# IRSensor.net
KiCad netlist of a schematic drawn in Altium Designer
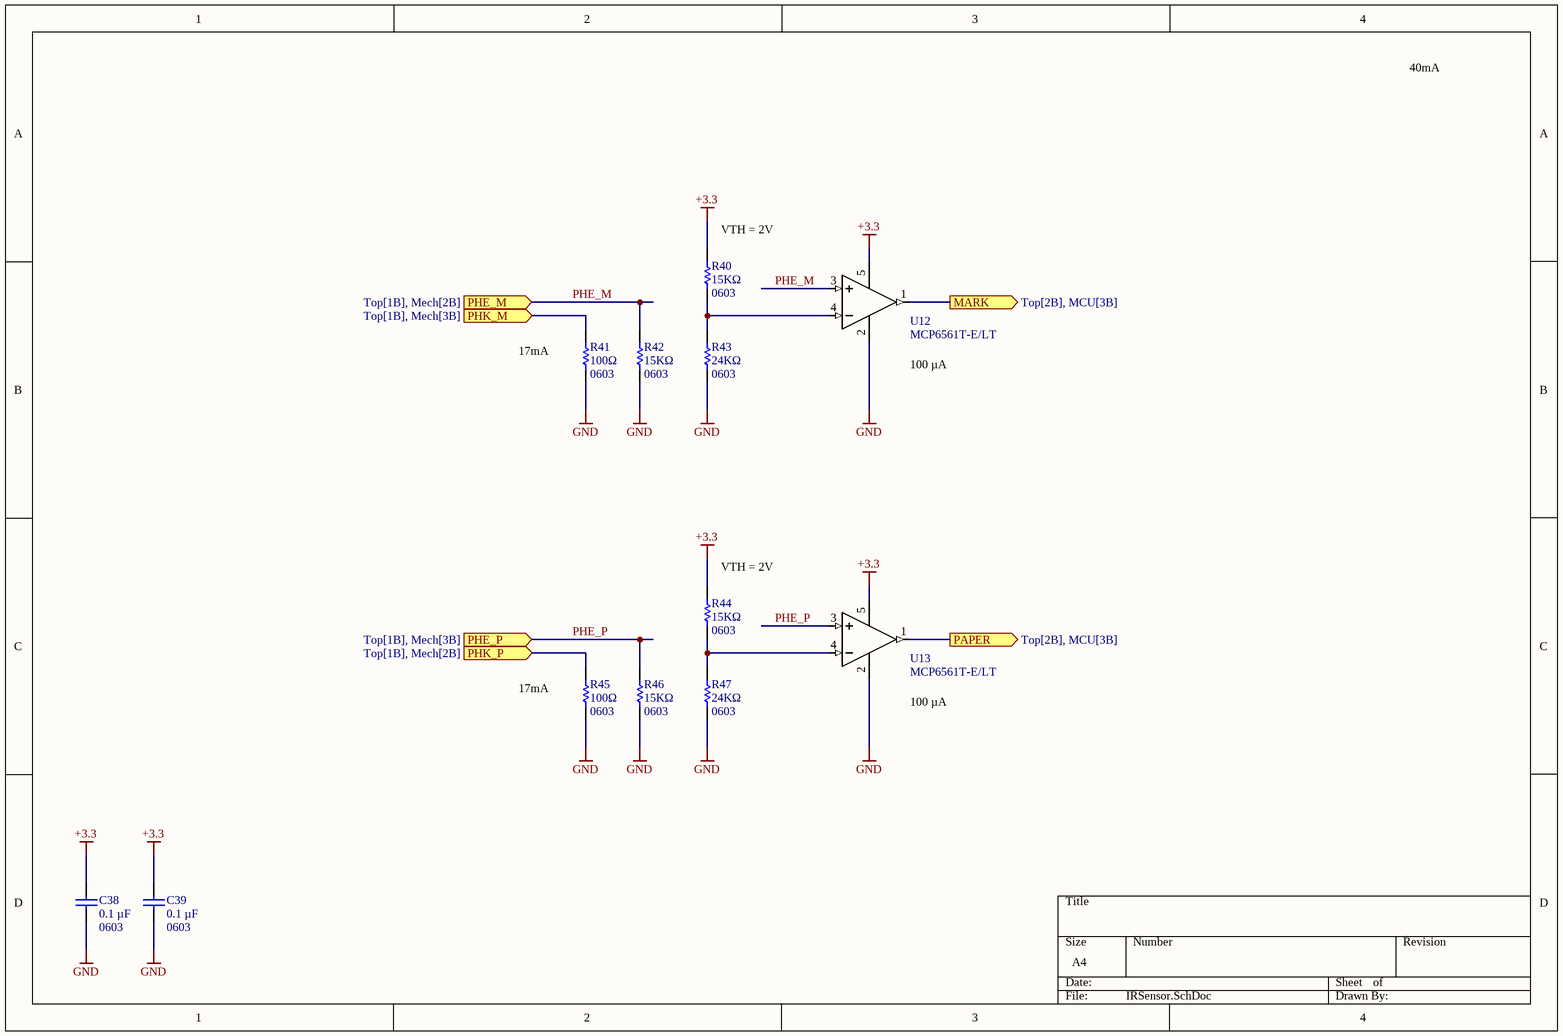
[diagram p0: IRSensor.SchDoc]

(export (version "E")
  (design (tool "Eeschema 10.0.6"))
  (components
    (comp (ref "C38")
      (value "0.1 µF")
      (footprint "0603")
      (description "0.1 µF ±20% 100V Ceramic Capacitor X7R 0603 (1608 Metric)")
      (fields (field (name "CASE") "0603") (field (name "TOLERANCE") "±20%") (field (name "VOLTAGE") "100V"))
      (libsource (lib "Murata Electronics") (part "GRM188R72A104MA35J"))
    )
    (comp (ref "C39")
      (value "0.1 µF")
      (footprint "0603")
      (description "0.1 µF ±20% 100V Ceramic Capacitor X7R 0603 (1608 Metric)")
      (fields (field (name "CASE") "0603") (field (name "TOLERANCE") "±20%") (field (name "VOLTAGE") "100V"))
      (libsource (lib "Murata Electronics") (part "GRM188R72A104MA35J"))
    )
    (comp (ref "R40")
      (value "15KΩ")
      (footprint "0603")
      (description "15 kOhms ±1% 0.1W, 1/10W Chip Resistor 0603 (1608 Metric) Automotive AEC-Q200 Thick Film")
      (fields (field (name "CASE") "0603") (field (name "TOLERANCE") "1%") (field (name "POWER") "0.1W"))
      (libsource (lib "Stackpole Electronics Inc") (part "RMCF0603FG15K0"))
    )
    (comp (ref "R41")
      (value "100Ω")
      (footprint "0603")
      (description "100 Ohms ±1% 0.1W, 1/10W Chip Resistor 0603 (1608 Metric) Automotive AEC-Q200 Thick Film")
      (fields (field (name "CASE") "0603") (field (name "TOLERANCE") "1%") (field (name "POWER") "0.1W"))
      (libsource (lib "Stackpole Electronics Inc") (part "RMCF0603FG100R"))
    )
    (comp (ref "R42")
      (value "15KΩ")
      (footprint "0603")
      (description "15 kOhms ±1% 0.1W, 1/10W Chip Resistor 0603 (1608 Metric) Automotive AEC-Q200 Thick Film")
      (fields (field (name "CASE") "0603") (field (name "TOLERANCE") "1%") (field (name "POWER") "0.1W"))
      (libsource (lib "Stackpole Electronics Inc") (part "RMCF0603FG15K0"))
    )
    (comp (ref "R43")
      (value "24KΩ")
      (footprint "0603")
      (description "24 kOhms ±1% 0.1W, 1/10W Chip Resistor 0603 (1608 Metric) Automotive AEC-Q200 Thick Film")
      (fields (field (name "CASE") "0603") (field (name "TOLERANCE") "1%") (field (name "POWER") "0.1W"))
      (libsource (lib "Stackpole Electronics Inc") (part "RMCF0603FG24K0"))
    )
    (comp (ref "R44")
      (value "15KΩ")
      (footprint "0603")
      (description "15 kOhms ±1% 0.1W, 1/10W Chip Resistor 0603 (1608 Metric) Automotive AEC-Q200 Thick Film")
      (fields (field (name "CASE") "0603") (field (name "TOLERANCE") "1%") (field (name "POWER") "0.1W"))
      (libsource (lib "Stackpole Electronics Inc") (part "RMCF0603FG15K0"))
    )
    (comp (ref "R45")
      (value "100Ω")
      (footprint "0603")
      (description "100 Ohms ±1% 0.1W, 1/10W Chip Resistor 0603 (1608 Metric) Automotive AEC-Q200 Thick Film")
      (fields (field (name "CASE") "0603") (field (name "TOLERANCE") "1%") (field (name "POWER") "0.1W"))
      (libsource (lib "Stackpole Electronics Inc") (part "RMCF0603FG100R"))
    )
    (comp (ref "R46")
      (value "15KΩ")
      (footprint "0603")
      (description "15 kOhms ±1% 0.1W, 1/10W Chip Resistor 0603 (1608 Metric) Automotive AEC-Q200 Thick Film")
      (fields (field (name "CASE") "0603") (field (name "TOLERANCE") "1%") (field (name "POWER") "0.1W"))
      (libsource (lib "Stackpole Electronics Inc") (part "RMCF0603FG15K0"))
    )
    (comp (ref "R47")
      (value "24KΩ")
      (footprint "0603")
      (description "24 kOhms ±1% 0.1W, 1/10W Chip Resistor 0603 (1608 Metric) Automotive AEC-Q200 Thick Film")
      (fields (field (name "CASE") "0603") (field (name "TOLERANCE") "1%") (field (name "POWER") "0.1W"))
      (libsource (lib "Stackpole Electronics Inc") (part "RMCF0603FG24K0"))
    )
    (comp (ref "U12")
      (value "MCP6561T-E/LT")
      (footprint "SC-70-5")
      (description "Comparator General Purpose CMOS, Push-Pull, Rail-to-Rail, TTL SC-70-5")
      (libsource (lib "Microchip Technology") (part "MCP6561T-E/LT"))
    )
    (comp (ref "U13")
      (value "MCP6561T-E/LT")
      (footprint "SC-70-5")
      (description "Comparator General Purpose CMOS, Push-Pull, Rail-to-Rail, TTL SC-70-5")
      (libsource (lib "Microchip Technology") (part "MCP6561T-E/LT"))
    )
  )
  (nets
    (net (code "1") (name "+3.3") (class "Default")
      (node (ref "C38") (pin "1") (pinfunction "1_1") (pintype "passive"))
      (node (ref "C39") (pin "1") (pinfunction "1_1") (pintype "passive"))
      (node (ref "R40") (pin "2") (pinfunction "2_2") (pintype "passive"))
      (node (ref "R44") (pin "2") (pinfunction "2_2") (pintype "passive"))
      (node (ref "U12") (pin "5") (pinfunction "V+_5") (pintype "power_in"))
      (node (ref "U13") (pin "5") (pinfunction "V+_5") (pintype "power_in"))
    )
    (net (code "2") (name "/MARK") (class "Default")
      (node (ref "U12") (pin "1") (pinfunction "OUT_1") (pintype "output"))
    )
    (net (code "3") (name "/PAPER") (class "Default")
      (node (ref "U13") (pin "1") (pinfunction "OUT_1") (pintype "output"))
    )
    (net (code "4") (name "/PHE_M") (class "Default")
      (node (ref "R42") (pin "2") (pinfunction "2_2") (pintype "passive"))
      (node (ref "U12") (pin "3") (pinfunction "+IN_3") (pintype "input"))
    )
    (net (code "5") (name "/PHE_P") (class "Default")
      (node (ref "R46") (pin "2") (pinfunction "2_2") (pintype "passive"))
      (node (ref "U13") (pin "3") (pinfunction "+IN_3") (pintype "input"))
    )
    (net (code "6") (name "/PHK_M") (class "Default")
      (node (ref "R41") (pin "2") (pinfunction "2_2") (pintype "passive"))
    )
    (net (code "7") (name "/PHK_P") (class "Default")
      (node (ref "R45") (pin "2") (pinfunction "2_2") (pintype "passive"))
    )
    (net (code "8") (name "GND") (class "Default")
      (node (ref "C38") (pin "2") (pinfunction "2_2") (pintype "passive"))
      (node (ref "C39") (pin "2") (pinfunction "2_2") (pintype "passive"))
      (node (ref "R41") (pin "1") (pinfunction "1_1") (pintype "passive"))
      (node (ref "R42") (pin "1") (pinfunction "1_1") (pintype "passive"))
      (node (ref "R43") (pin "1") (pinfunction "1_1") (pintype "passive"))
      (node (ref "R45") (pin "1") (pinfunction "1_1") (pintype "passive"))
      (node (ref "R46") (pin "1") (pinfunction "1_1") (pintype "passive"))
      (node (ref "R47") (pin "1") (pinfunction "1_1") (pintype "passive"))
      (node (ref "U12") (pin "2") (pinfunction "V-_2") (pintype "power_in"))
      (node (ref "U13") (pin "2") (pinfunction "V-_2") (pintype "power_in"))
    )
    (net (code "9") (name "Net-(U12--IN)") (class "Default")
      (node (ref "R40") (pin "1") (pinfunction "1_1") (pintype "passive"))
      (node (ref "R43") (pin "2") (pinfunction "2_2") (pintype "passive"))
      (node (ref "U12") (pin "4") (pinfunction "-IN_4") (pintype "input"))
    )
    (net (code "10") (name "Net-(U13--IN)") (class "Default")
      (node (ref "R44") (pin "1") (pinfunction "1_1") (pintype "passive"))
      (node (ref "R47") (pin "2") (pinfunction "2_2") (pintype "passive"))
      (node (ref "U13") (pin "4") (pinfunction "-IN_4") (pintype "input"))
    )
  )
)
